# Section_3_2020-11-02_18-49-52.net
KiCad netlist of a schematic drawn in EasyEDA
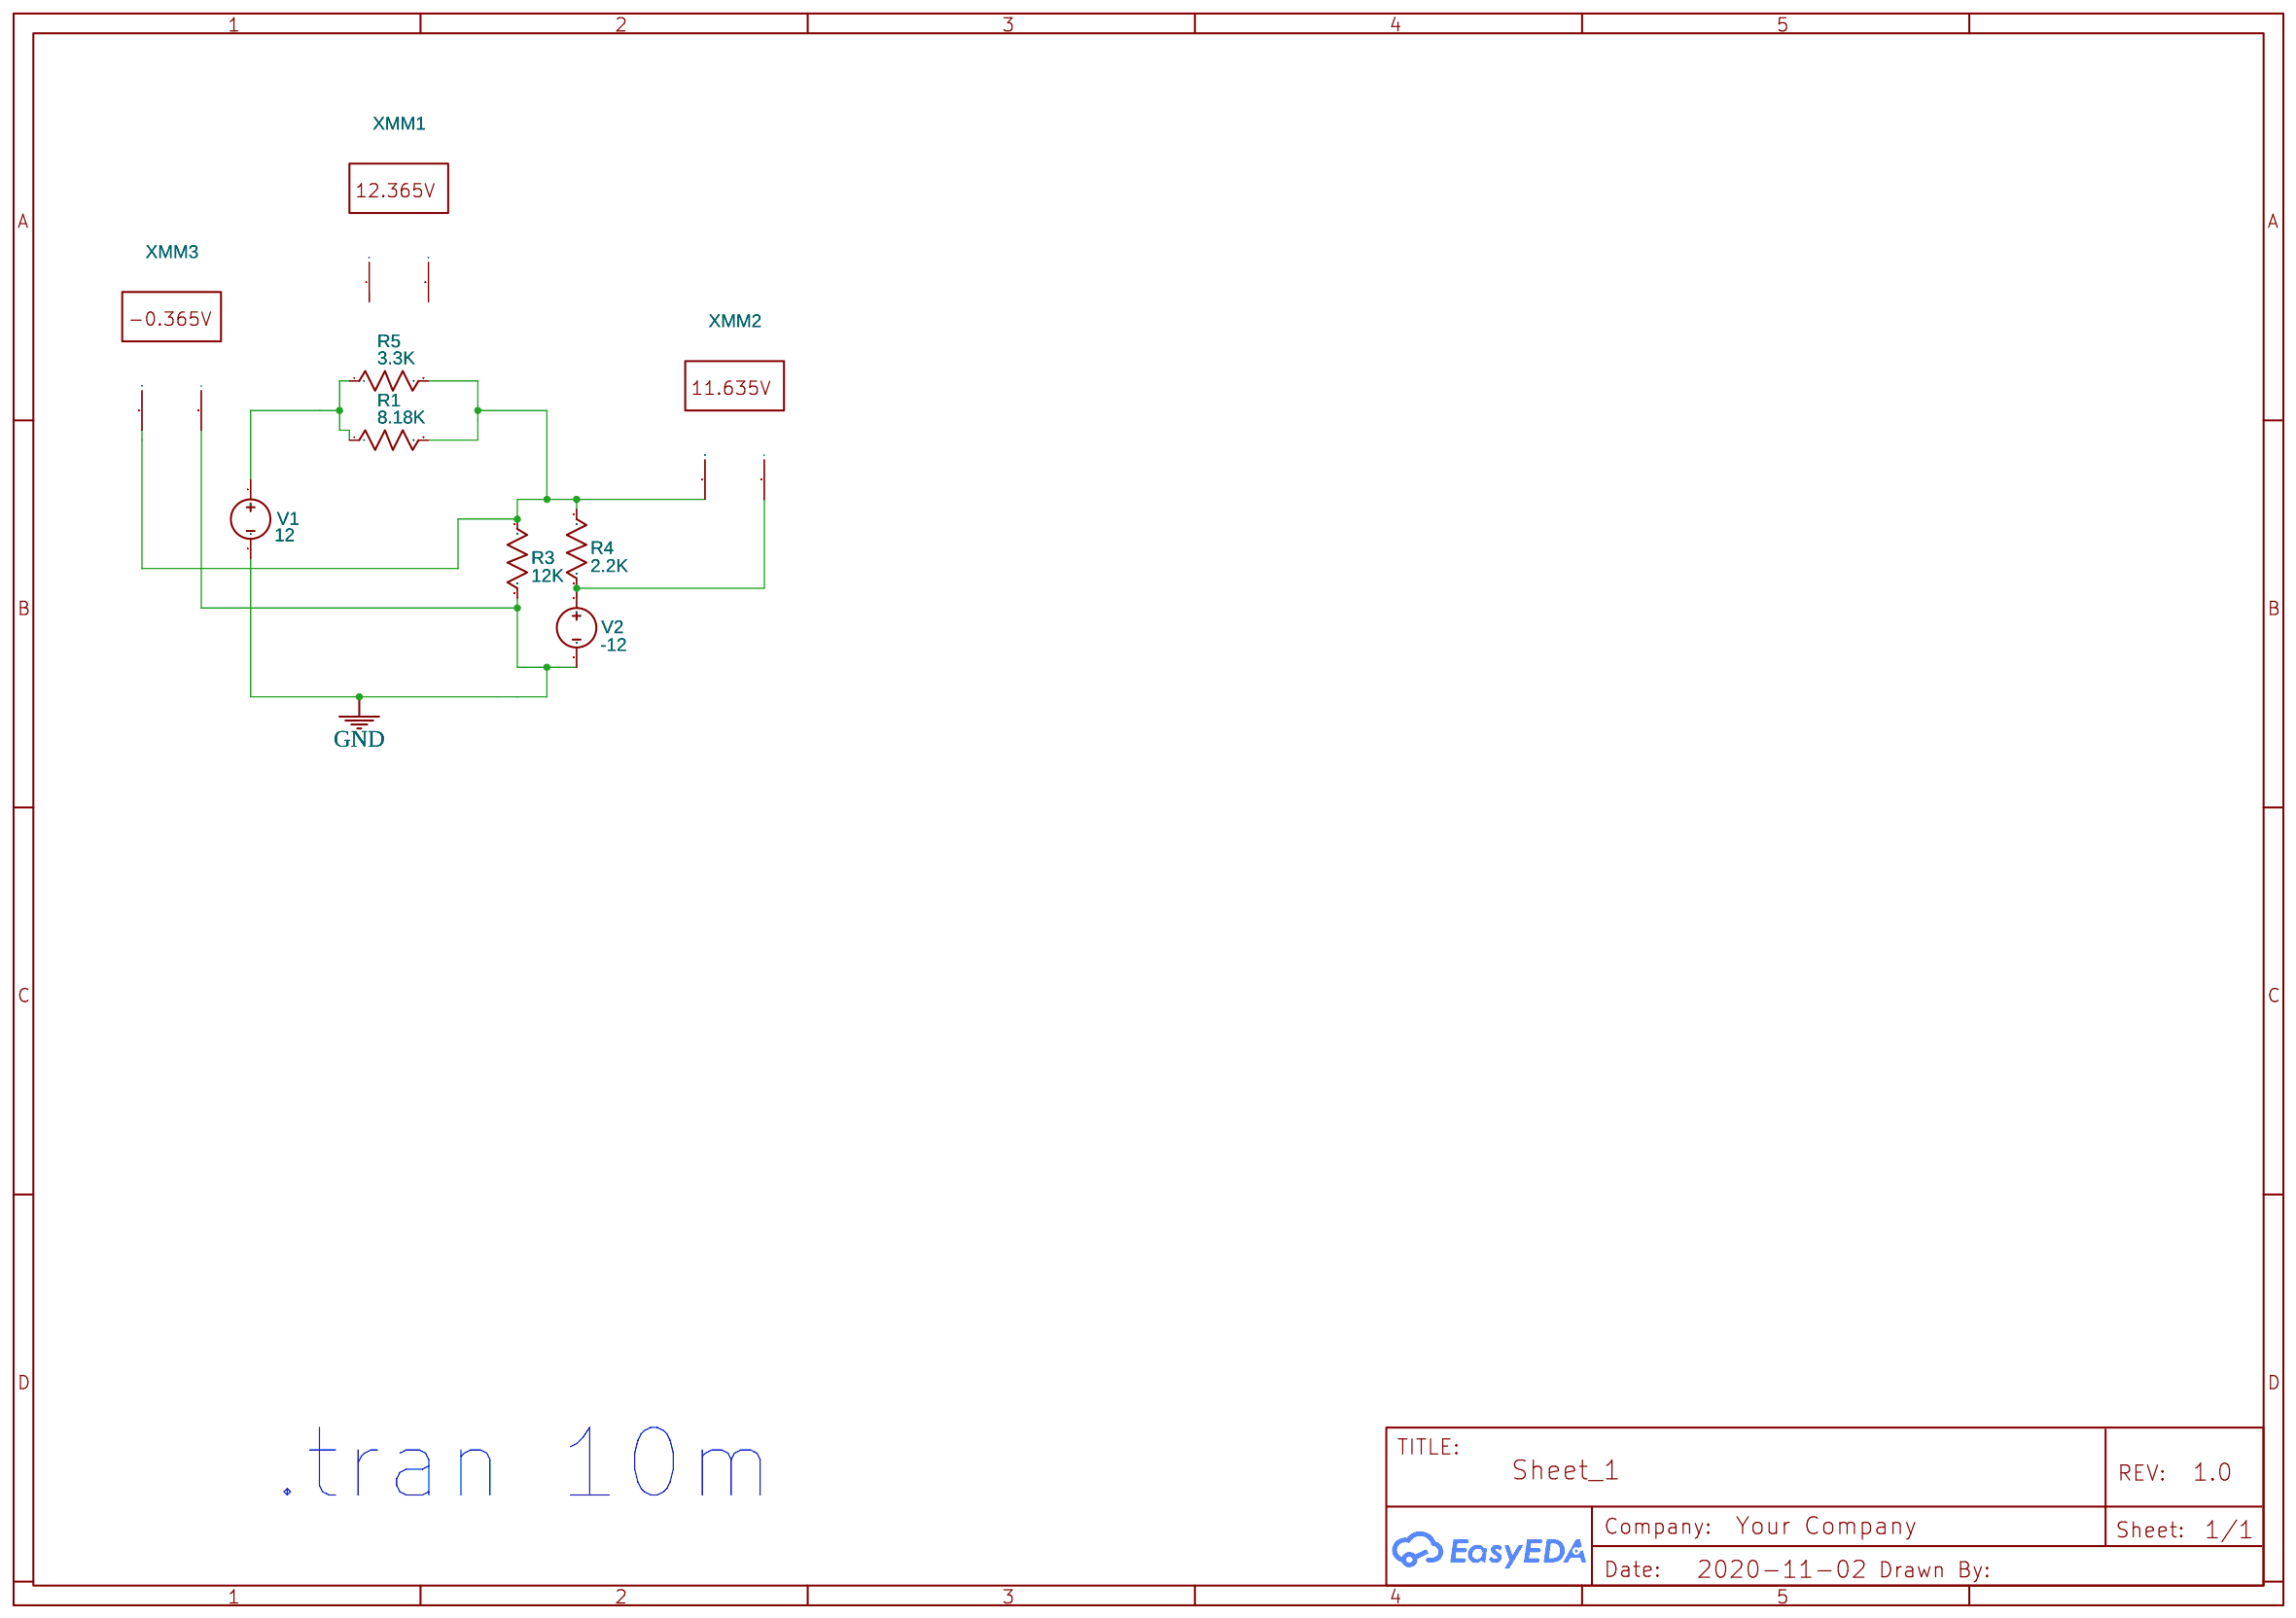
[diagram p0: schematic sheet]

(export (version "E")
  (design (tool "Eeschema 10.0.6"))
  (components
    (comp (ref "R1") (value "8.18K") (libsource (lib "") (part "Resistor_US")))
    (comp (ref "R3") (value "12K") (libsource (lib "") (part "Resistor_US_1")))
    (comp (ref "R4") (value "2.2K") (libsource (lib "") (part "Resistor_US_1")))
    (comp (ref "R5") (value "3.3K") (libsource (lib "") (part "Resistor_US")))
    (comp (ref "V1") (value "12") (libsource (lib "") (part "VDC")))
    (comp (ref "V2") (value "-12") (libsource (lib "") (part "VDC")))
    (comp (ref "XMM1") (value "Multimeter") (libsource (lib "") (part "MULTIMETER_2")))
    (comp (ref "XMM2") (value "Multimeter") (libsource (lib "") (part "MULTIMETER")))
    (comp (ref "XMM3") (value "Multimeter") (libsource (lib "") (part "MULTIMETER_1")))
  )
  (nets
    (net (code "1") (name "GND") (class "Default")
      (node (ref "R3") (pin "2") (pinfunction "2_2") (pintype "unspecified"))
      (node (ref "V1") (pin "2") (pinfunction "2_2") (pintype "unspecified"))
      (node (ref "V2") (pin "2") (pinfunction "2_2") (pintype "unspecified"))
      (node (ref "XMM3") (pin "2") (pinfunction "I_2") (pintype "unspecified"))
    )
    (net (code "2") (name "Net-(R1-Pad1)") (class "Default")
      (node (ref "R1") (pin "1") (pinfunction "1_1") (pintype "unspecified"))
      (node (ref "R5") (pin "1") (pinfunction "1_1") (pintype "unspecified"))
      (node (ref "V1") (pin "1") (pinfunction "1_1") (pintype "unspecified"))
    )
    (net (code "3") (name "Net-(XMM2-+)") (class "Default")
      (node (ref "R1") (pin "2") (pinfunction "2_2") (pintype "unspecified"))
      (node (ref "R3") (pin "1") (pinfunction "1_1") (pintype "unspecified"))
      (node (ref "R4") (pin "1") (pinfunction "1_1") (pintype "unspecified"))
      (node (ref "R5") (pin "2") (pinfunction "2_2") (pintype "unspecified"))
      (node (ref "XMM2") (pin "1") (pinfunction "+_1") (pintype "unspecified"))
      (node (ref "XMM3") (pin "1") (pinfunction "+_1") (pintype "unspecified"))
    )
    (net (code "4") (name "Net-(XMM2-I)") (class "Default")
      (node (ref "R4") (pin "2") (pinfunction "2_2") (pintype "unspecified"))
      (node (ref "V2") (pin "1") (pinfunction "1_1") (pintype "unspecified"))
      (node (ref "XMM2") (pin "2") (pinfunction "I_2") (pintype "unspecified"))
    )
    (net (code "5") (name "unconnected-(XMM1-+-Pad1)") (class "Default")
      (node (ref "XMM1") (pin "1") (pinfunction "+_1") (pintype "unspecified"))
    )
    (net (code "6") (name "unconnected-(XMM1-I-Pad2)") (class "Default")
      (node (ref "XMM1") (pin "2") (pinfunction "I_2") (pintype "unspecified"))
    )
  )
)
